# smartwatch_class_2.net
KiCad netlist of a schematic drawn in EAGLE
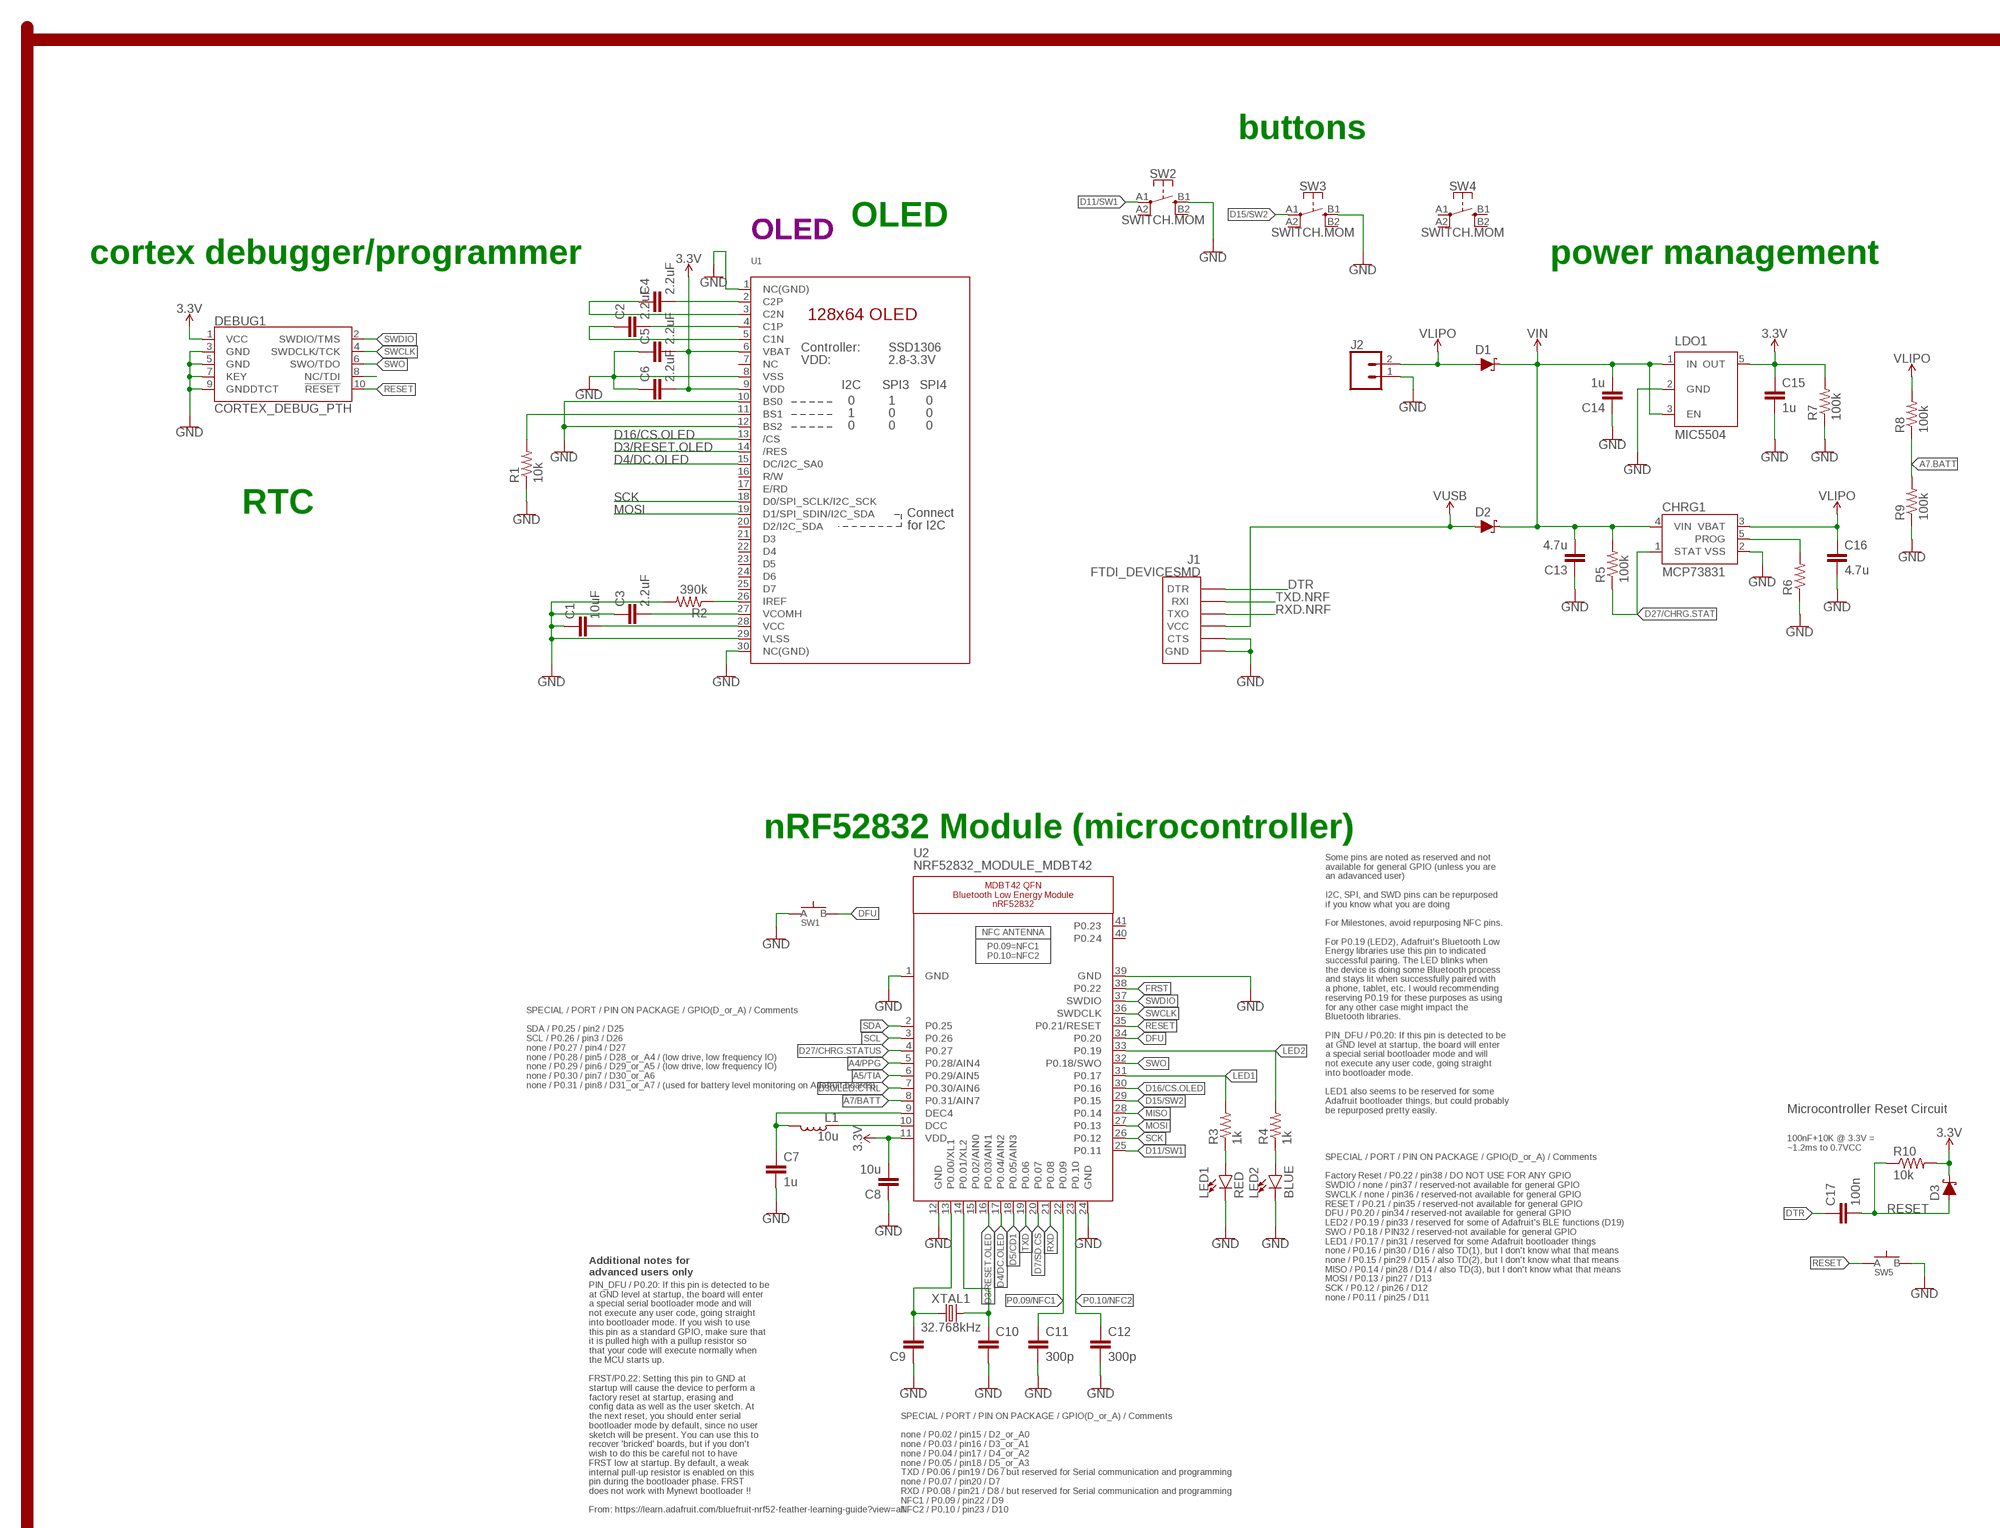
[diagram p0: schematic, sheet 1, part 1 of 2]
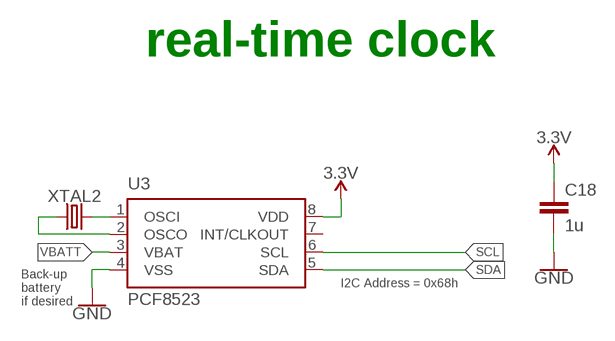
[diagram p1: schematic, sheet 1, part 2 of 2]

(export (version "E")
  (design (tool "Eeschema 10.0.6"))
  (components
    (comp (ref "C1")
      (value "10uF")
      (footprint "eagle-import:C0603")
      (libsource (lib "eagle-import") (part "CAPACITOR0603"))
    )
    (comp (ref "C2")
      (value "2.2uF")
      (footprint "eagle-import:C0402")
      (libsource (lib "eagle-import") (part "CAPACITOR0402"))
    )
    (comp (ref "C3")
      (value "2.2uF")
      (footprint "eagle-import:C0402")
      (libsource (lib "eagle-import") (part "CAPACITOR0402"))
    )
    (comp (ref "C4")
      (value "2.2uF")
      (footprint "eagle-import:C0402")
      (libsource (lib "eagle-import") (part "CAPACITOR0402"))
    )
    (comp (ref "C5")
      (value "2.2uF")
      (footprint "eagle-import:C0402")
      (libsource (lib "eagle-import") (part "CAPACITOR0402"))
    )
    (comp (ref "C6")
      (value "2.2uF")
      (footprint "eagle-import:C0402")
      (libsource (lib "eagle-import") (part "CAPACITOR0402"))
    )
    (comp (ref "C7")
      (value "1u")
      (footprint "eagle-import:C0603")
      (libsource (lib "eagle-import") (part "CAPACITOR0603"))
    )
    (comp (ref "C8")
      (value "10u")
      (footprint "eagle-import:C0805")
      (libsource (lib "eagle-import") (part "CAPACITOR0805"))
    )
    (comp (ref "C9")
      (value "CAPACITOR0603")
      (footprint "eagle-import:C0603")
      (libsource (lib "eagle-import") (part "CAPACITOR0603"))
    )
    (comp (ref "C10")
      (value "CAPACITOR0603")
      (footprint "eagle-import:C0603")
      (libsource (lib "eagle-import") (part "CAPACITOR0603"))
    )
    (comp (ref "C11")
      (value "300p")
      (footprint "eagle-import:C0603")
      (libsource (lib "eagle-import") (part "CAPACITOR0603"))
    )
    (comp (ref "C12")
      (value "300p")
      (footprint "eagle-import:C0603")
      (libsource (lib "eagle-import") (part "CAPACITOR0603"))
    )
    (comp (ref "C13")
      (value "4.7u")
      (footprint "eagle-import:C0603")
      (libsource (lib "eagle-import") (part "CAPACITOR0603"))
    )
    (comp (ref "C14")
      (value "1u")
      (footprint "eagle-import:C0603")
      (libsource (lib "eagle-import") (part "CAPACITOR0603"))
    )
    (comp (ref "C15")
      (value "1u")
      (footprint "eagle-import:C0603")
      (libsource (lib "eagle-import") (part "CAPACITOR0603"))
    )
    (comp (ref "C16")
      (value "4.7u")
      (footprint "eagle-import:C0603")
      (libsource (lib "eagle-import") (part "CAPACITOR0603"))
    )
    (comp (ref "C17")
      (value "100n")
      (footprint "eagle-import:C0603")
      (libsource (lib "eagle-import") (part "CAPACITOR0603"))
    )
    (comp (ref "C18")
      (value "1u")
      (footprint "eagle-import:C0603")
      (libsource (lib "eagle-import") (part "CAPACITOR0603"))
    )
    (comp (ref "CHRG1")
      (value "MCP73831")
      (footprint "eagle-import:SOT23-5")
      (libsource (lib "eagle-import") (part "MCP73831"))
    )
    (comp (ref "D1")
      (value "SCHOTTKY-USC")
      (footprint "eagle-import:USC")
      (libsource (lib "eagle-import") (part "SCHOTTKY-USC"))
    )
    (comp (ref "D2")
      (value "SCHOTTKY-USC")
      (footprint "eagle-import:USC")
      (libsource (lib "eagle-import") (part "SCHOTTKY-USC"))
    )
    (comp (ref "D3")
      (value "SCHOTTKY-USC")
      (footprint "eagle-import:USC")
      (libsource (lib "eagle-import") (part "SCHOTTKY-USC"))
    )
    (comp (ref "DEBUG1")
      (value "CORTEX_DEBUG_PTH")
      (footprint "eagle-import:2X5-PTH-1.27MM")
      (libsource (lib "eagle-import") (part "CORTEX_DEBUG_PTH"))
    )
    (comp (ref "J1")
      (value "FTDI_DEVICESMD")
      (footprint "eagle-import:FTDI-SMD")
      (libsource (lib "eagle-import") (part "FTDI_DEVICESMD"))
    )
    (comp (ref "J2")
      (value "CONN_02")
      (footprint "eagle-import:1X02")
      (libsource (lib "eagle-import") (part "CONN_02"))
    )
    (comp (ref "L1")
      (value "10u")
      (footprint "eagle-import:L0603")
      (libsource (lib "eagle-import") (part "INDUCTOR0603"))
    )
    (comp (ref "LDO1")
      (value "MIC5504")
      (footprint "eagle-import:SOT23-5")
      (libsource (lib "eagle-import") (part "MIC5504"))
    )
    (comp (ref "LED1")
      (value "RED")
      (footprint "eagle-import:LED-0603")
      (libsource (lib "eagle-import") (part "LED0603"))
    )
    (comp (ref "LED2")
      (value "BLUE")
      (footprint "eagle-import:LED-0603")
      (libsource (lib "eagle-import") (part "LED0603"))
    )
    (comp (ref "R1")
      (value "10k")
      (footprint "eagle-import:R0603")
      (libsource (lib "eagle-import") (part "RESISTOR0603"))
    )
    (comp (ref "R2")
      (value "390k")
      (footprint "eagle-import:R0603")
      (libsource (lib "eagle-import") (part "RESISTOR0603"))
    )
    (comp (ref "R3")
      (value "1k")
      (footprint "eagle-import:R0603")
      (libsource (lib "eagle-import") (part "RESISTOR0603"))
    )
    (comp (ref "R4")
      (value "1k")
      (footprint "eagle-import:R0603")
      (libsource (lib "eagle-import") (part "RESISTOR0603"))
    )
    (comp (ref "R5")
      (value "100k")
      (footprint "eagle-import:R0603")
      (libsource (lib "eagle-import") (part "RESISTOR0603"))
    )
    (comp (ref "R6")
      (value "RESISTOR0603")
      (footprint "eagle-import:R0603")
      (libsource (lib "eagle-import") (part "RESISTOR0603"))
    )
    (comp (ref "R7")
      (value "100k")
      (footprint "eagle-import:R0603")
      (libsource (lib "eagle-import") (part "RESISTOR0603"))
    )
    (comp (ref "R8")
      (value "100k")
      (footprint "eagle-import:R0603")
      (libsource (lib "eagle-import") (part "RESISTOR0603"))
    )
    (comp (ref "R9")
      (value "100k")
      (footprint "eagle-import:R0603")
      (libsource (lib "eagle-import") (part "RESISTOR0603"))
    )
    (comp (ref "R10")
      (value "10k")
      (footprint "eagle-import:R0603")
      (libsource (lib "eagle-import") (part "RESISTOR0603"))
    )
    (comp (ref "SW1")
      (value "SPST-PTS830GG140-COPY.1-3")
      (footprint "eagle-import:BUTTON-GULLWING")
      (libsource (lib "eagle-import") (part "SPST-PTS830GG140-COPY.1-3"))
    )
    (comp (ref "SW2")
      (value "SWITCH.MOM")
      (footprint "eagle-import:TACTILE_SWITCH_SMD_6.2MM_TALL")
      (libsource (lib "eagle-import") (part "SWITCH.MOM"))
    )
    (comp (ref "SW3")
      (value "SWITCH.MOM")
      (footprint "eagle-import:TACTILE_SWITCH_SMD_6.2MM_TALL")
      (libsource (lib "eagle-import") (part "SWITCH.MOM"))
    )
    (comp (ref "SW4")
      (value "SWITCH.MOM")
      (footprint "eagle-import:TACTILE_SWITCH_SMD_6.2MM_TALL")
      (libsource (lib "eagle-import") (part "SWITCH.MOM"))
    )
    (comp (ref "SW5")
      (value "SPST-PTS830GG140-COPY.1-3")
      (footprint "eagle-import:BUTTON-GULLWING")
      (libsource (lib "eagle-import") (part "SPST-PTS830GG140-COPY.1-3"))
    )
    (comp (ref "U1")
      (value "DISP_OLED_UG-2864HSWEG01-NO-WRAPAROUND")
      (footprint "eagle-import:UG-2864HSWEG01_0.96IN_NO-WRAPAROUND")
      (libsource (lib "eagle-import") (part "DISP_OLED_UG-2864HSWEG01-NO-WRAPAROUND"))
    )
    (comp (ref "U2")
      (value "NRF52832_MODULE_MDBT42")
      (footprint "eagle-import:BLE_MODULE_RAYTAC_MDBT42")
      (libsource (lib "eagle-import") (part "NRF52832_MODULE_MDBT42"))
    )
    (comp (ref "U3")
      (value "PCF8523")
      (footprint "eagle-import:SO8")
      (libsource (lib "eagle-import") (part "PCF8523"))
    )
    (comp (ref "XTAL1")
      (value "32.768kHz")
      (footprint "eagle-import:2-SMD.NOLEAD.2.0MMTO1.2MM")
      (libsource (lib "eagle-import") (part "CRYSTALECS-.327-12.5-12-C-TR"))
    )
    (comp (ref "XTAL2")
      (value "32.7680kHz")
      (footprint "eagle-import:2-SMD.NOLEAD.2.0MMTO1.2MM")
      (fields (field (name "FREQ") "32.7680KHZ"))
      (libsource (lib "eagle-import") (part "CRYSTALECS-.327-12.5-12-C-TR"))
    )
  )
  (nets
    (net (code "1") (name "/RXD.NRF") (class "Default")
      (node (ref "J1") (pin "TXO") (pinfunction "TXO_TXO") (pintype "bidirectional"))
    )
    (net (code "2") (name "/TXD.NRF") (class "Default")
      (node (ref "J1") (pin "RXI") (pinfunction "RXI_RXI") (pintype "bidirectional"))
    )
    (net (code "3") (name "3.3V") (class "Default")
      (node (ref "C15") (pin "1") (pinfunction "1_1") (pintype "passive"))
      (node (ref "C18") (pin "1") (pinfunction "1_1") (pintype "passive"))
      (node (ref "C5") (pin "2") (pinfunction "2_2") (pintype "passive"))
      (node (ref "C6") (pin "2") (pinfunction "2_2") (pintype "passive"))
      (node (ref "C8") (pin "2") (pinfunction "2_2") (pintype "passive"))
      (node (ref "D3") (pin "-") (pinfunction "C_-") (pintype "passive"))
      (node (ref "DEBUG1") (pin "1") (pinfunction "VCC_1") (pintype "bidirectional"))
      (node (ref "LDO1") (pin "5") (pinfunction "OUT_5") (pintype "bidirectional"))
      (node (ref "R10") (pin "2") (pinfunction "2_2") (pintype "passive"))
      (node (ref "R7") (pin "2") (pinfunction "2_2") (pintype "passive"))
      (node (ref "U1") (pin "6") (pinfunction "VBAT_6") (pintype "input"))
      (node (ref "U1") (pin "9") (pinfunction "VDD_9") (pintype "power_in"))
      (node (ref "U2") (pin "11") (pinfunction "VDD_11") (pintype "bidirectional"))
      (node (ref "U3") (pin "8") (pinfunction "VDD_8") (pintype "power_in"))
    )
    (net (code "4") (name "A4{slash}PPG") (class "Default")
      (node (ref "U2") (pin "5") (pinfunction "P0.28/AIN4_5") (pintype "bidirectional"))
    )
    (net (code "5") (name "A5{slash}TIA") (class "Default")
      (node (ref "U2") (pin "6") (pinfunction "P0.29/AIN5_6") (pintype "bidirectional"))
    )
    (net (code "6") (name "A7.BATT") (class "Default")
      (node (ref "R8") (pin "1") (pinfunction "1_1") (pintype "passive"))
      (node (ref "R9") (pin "2") (pinfunction "2_2") (pintype "passive"))
    )
    (net (code "7") (name "A7{slash}BATT") (class "Default")
      (node (ref "U2") (pin "8") (pinfunction "P0.31/AIN7_8") (pintype "bidirectional"))
    )
    (net (code "8") (name "D3{slash}RESET.OLED") (class "Default")
      (node (ref "U1") (pin "14") (pinfunction "/RES_14") (pintype "input"))
      (node (ref "U2") (pin "16") (pinfunction "P0.03/AIN1_16") (pintype "bidirectional"))
    )
    (net (code "9") (name "D4{slash}DC.OLED") (class "Default")
      (node (ref "U1") (pin "15") (pinfunction "DC/I2C_SA0_15") (pintype "input"))
      (node (ref "U2") (pin "17") (pinfunction "P0.04/AIN2_17") (pintype "bidirectional"))
    )
    (net (code "10") (name "D5{slash}CD1") (class "Default")
      (node (ref "U2") (pin "18") (pinfunction "P0.05/AIN3_18") (pintype "bidirectional"))
    )
    (net (code "11") (name "D7{slash}SD.CS") (class "Default")
      (node (ref "U2") (pin "20") (pinfunction "P0.07_20") (pintype "bidirectional"))
    )
    (net (code "12") (name "D11{slash}SW1") (class "Default")
      (node (ref "SW2") (pin "A1") (pinfunction "1_A1") (pintype "passive"))
      (node (ref "U2") (pin "25") (pinfunction "P0.11_25") (pintype "bidirectional"))
    )
    (net (code "13") (name "D15{slash}SW2") (class "Default")
      (node (ref "SW3") (pin "A1") (pinfunction "1_A1") (pintype "passive"))
      (node (ref "U2") (pin "29") (pinfunction "P0.15_29") (pintype "bidirectional"))
    )
    (net (code "14") (name "D16{slash}CS.OLED") (class "Default")
      (node (ref "U1") (pin "13") (pinfunction "/CS_13") (pintype "input"))
      (node (ref "U2") (pin "30") (pinfunction "P0.16_30") (pintype "bidirectional"))
    )
    (net (code "15") (name "D27{slash}CHRG.STAT") (class "Default")
      (node (ref "CHRG1") (pin "1") (pinfunction "STAT_1") (pintype "output"))
      (node (ref "R5") (pin "1") (pinfunction "1_1") (pintype "passive"))
    )
    (net (code "16") (name "D27{slash}CHRG.STATUS") (class "Default")
      (node (ref "U2") (pin "4") (pinfunction "P0.27_4") (pintype "bidirectional"))
    )
    (net (code "17") (name "D30{slash}LED.CTRL") (class "Default")
      (node (ref "U2") (pin "7") (pinfunction "P0.30/AIN6_7") (pintype "bidirectional"))
    )
    (net (code "18") (name "DFU") (class "Default")
      (node (ref "SW1") (pin "3") (pinfunction "B_3") (pintype "bidirectional"))
      (node (ref "U2") (pin "34") (pinfunction "P0.20_34") (pintype "bidirectional"))
    )
    (net (code "19") (name "DTR") (class "Default")
      (node (ref "C17") (pin "1") (pinfunction "1_1") (pintype "passive"))
      (node (ref "J1") (pin "DTR") (pinfunction "DTR_DTR") (pintype "bidirectional"))
    )
    (net (code "20") (name "FRST") (class "Default")
      (node (ref "U2") (pin "38") (pinfunction "P0.22_38") (pintype "bidirectional"))
    )
    (net (code "21") (name "GND") (class "Default")
      (node (ref "C1") (pin "1") (pinfunction "1_1") (pintype "passive"))
      (node (ref "C10") (pin "2") (pinfunction "2_2") (pintype "passive"))
      (node (ref "C11") (pin "2") (pinfunction "2_2") (pintype "passive"))
      (node (ref "C12") (pin "2") (pinfunction "2_2") (pintype "passive"))
      (node (ref "C13") (pin "1") (pinfunction "1_1") (pintype "passive"))
      (node (ref "C14") (pin "1") (pinfunction "1_1") (pintype "passive"))
      (node (ref "C15") (pin "2") (pinfunction "2_2") (pintype "passive"))
      (node (ref "C16") (pin "2") (pinfunction "2_2") (pintype "passive"))
      (node (ref "C18") (pin "2") (pinfunction "2_2") (pintype "passive"))
      (node (ref "C3") (pin "1") (pinfunction "1_1") (pintype "passive"))
      (node (ref "C5") (pin "1") (pinfunction "1_1") (pintype "passive"))
      (node (ref "C6") (pin "1") (pinfunction "1_1") (pintype "passive"))
      (node (ref "C7") (pin "2") (pinfunction "2_2") (pintype "passive"))
      (node (ref "C8") (pin "1") (pinfunction "1_1") (pintype "passive"))
      (node (ref "C9") (pin "1") (pinfunction "1_1") (pintype "passive"))
      (node (ref "CHRG1") (pin "2") (pinfunction "VSS_2") (pintype "power_in"))
      (node (ref "DEBUG1") (pin "3") (pinfunction "GND_3") (pintype "bidirectional"))
      (node (ref "DEBUG1") (pin "5") (pinfunction "GND_5") (pintype "bidirectional"))
      (node (ref "DEBUG1") (pin "7") (pinfunction "KEY_7") (pintype "bidirectional"))
      (node (ref "DEBUG1") (pin "9") (pinfunction "GNDDTCT_9") (pintype "bidirectional"))
      (node (ref "J1") (pin "CTS") (pinfunction "CTS_CTS") (pintype "bidirectional"))
      (node (ref "J1") (pin "GND") (pinfunction "GND_GND") (pintype "bidirectional"))
      (node (ref "J2") (pin "1") (pinfunction "1_1") (pintype "passive"))
      (node (ref "LDO1") (pin "2") (pinfunction "GND_2") (pintype "bidirectional"))
      (node (ref "LED1") (pin "C") (pinfunction "C_C") (pintype "passive"))
      (node (ref "LED2") (pin "C") (pinfunction "C_C") (pintype "passive"))
      (node (ref "R1") (pin "1") (pinfunction "1_1") (pintype "passive"))
      (node (ref "R2") (pin "2") (pinfunction "2_2") (pintype "passive"))
      (node (ref "R6") (pin "1") (pinfunction "1_1") (pintype "passive"))
      (node (ref "R7") (pin "1") (pinfunction "1_1") (pintype "passive"))
      (node (ref "R9") (pin "1") (pinfunction "1_1") (pintype "passive"))
      (node (ref "SW1") (pin "1") (pinfunction "A_1") (pintype "bidirectional"))
      (node (ref "SW2") (pin "B1") (pinfunction "3_B1") (pintype "passive"))
      (node (ref "SW3") (pin "B1") (pinfunction "3_B1") (pintype "passive"))
      (node (ref "SW5") (pin "3") (pinfunction "B_3") (pintype "bidirectional"))
      (node (ref "U1") (pin "1") (pinfunction "NC(GND)_1") (pintype "input"))
      (node (ref "U1") (pin "10") (pinfunction "BS0_10") (pintype "input"))
      (node (ref "U1") (pin "12") (pinfunction "BS2_12") (pintype "input"))
      (node (ref "U1") (pin "29") (pinfunction "VLSS_29") (pintype "power_in"))
      (node (ref "U1") (pin "30") (pinfunction "NC(GND)_30") (pintype "input"))
      (node (ref "U1") (pin "8") (pinfunction "VSS_8") (pintype "power_in"))
      (node (ref "U2") (pin "1") (pinfunction "GND_1") (pintype "bidirectional"))
      (node (ref "U2") (pin "12") (pinfunction "GND_12") (pintype "bidirectional"))
      (node (ref "U2") (pin "24") (pinfunction "GND_24") (pintype "bidirectional"))
      (node (ref "U2") (pin "39") (pinfunction "GND_39") (pintype "bidirectional"))
      (node (ref "U3") (pin "4") (pinfunction "VSS_4") (pintype "power_in"))
    )
    (net (code "22") (name "LED1") (class "Default")
      (node (ref "R3") (pin "2") (pinfunction "2_2") (pintype "passive"))
      (node (ref "U2") (pin "31") (pinfunction "P0.17_31") (pintype "bidirectional"))
    )
    (net (code "23") (name "LED2") (class "Default")
      (node (ref "R4") (pin "2") (pinfunction "2_2") (pintype "passive"))
      (node (ref "U2") (pin "33") (pinfunction "P0.19_33") (pintype "bidirectional"))
    )
    (net (code "24") (name "MISO") (class "Default")
      (node (ref "U2") (pin "28") (pinfunction "P0.14_28") (pintype "bidirectional"))
    )
    (net (code "25") (name "MOSI") (class "Default")
      (node (ref "U1") (pin "19") (pinfunction "D1/SPI_SDIN/I2C_SDA_19") (pintype "bidirectional"))
      (node (ref "U2") (pin "27") (pinfunction "P0.13_27") (pintype "bidirectional"))
    )
    (net (code "26") (name "Net-(CHRG1-PROG)") (class "Default")
      (node (ref "CHRG1") (pin "5") (pinfunction "PROG_5") (pintype "input"))
      (node (ref "R6") (pin "2") (pinfunction "2_2") (pintype "passive"))
    )
    (net (code "27") (name "Net-(LED1-PadA)") (class "Default")
      (node (ref "LED1") (pin "A") (pinfunction "A_A") (pintype "passive"))
      (node (ref "R3") (pin "1") (pinfunction "1_1") (pintype "passive"))
    )
    (net (code "28") (name "Net-(LED2-PadA)") (class "Default")
      (node (ref "LED2") (pin "A") (pinfunction "A_A") (pintype "passive"))
      (node (ref "R4") (pin "1") (pinfunction "1_1") (pintype "passive"))
    )
    (net (code "29") (name "Net-(U1-BS1)") (class "Default")
      (node (ref "R1") (pin "2") (pinfunction "2_2") (pintype "passive"))
      (node (ref "U1") (pin "11") (pinfunction "BS1_11") (pintype "input"))
    )
    (net (code "30") (name "Net-(U1-C1N)") (class "Default")
      (node (ref "C2") (pin "1") (pinfunction "1_1") (pintype "passive"))
      (node (ref "U1") (pin "5") (pinfunction "C1N_5") (pintype "input"))
    )
    (net (code "31") (name "Net-(U1-C1P)") (class "Default")
      (node (ref "C2") (pin "2") (pinfunction "2_2") (pintype "passive"))
      (node (ref "U1") (pin "4") (pinfunction "C1P_4") (pintype "input"))
    )
    (net (code "32") (name "Net-(U1-C2N)") (class "Default")
      (node (ref "C4") (pin "1") (pinfunction "1_1") (pintype "passive"))
      (node (ref "U1") (pin "3") (pinfunction "C2N_3") (pintype "input"))
    )
    (net (code "33") (name "Net-(U1-C2P)") (class "Default")
      (node (ref "C4") (pin "2") (pinfunction "2_2") (pintype "passive"))
      (node (ref "U1") (pin "2") (pinfunction "C2P_2") (pintype "input"))
    )
    (net (code "34") (name "Net-(U1-IREF)") (class "Default")
      (node (ref "R2") (pin "1") (pinfunction "1_1") (pintype "passive"))
      (node (ref "U1") (pin "26") (pinfunction "IREF_26") (pintype "input"))
    )
    (net (code "35") (name "Net-(U1-VCC)") (class "Default")
      (node (ref "C1") (pin "2") (pinfunction "2_2") (pintype "passive"))
      (node (ref "U1") (pin "28") (pinfunction "VCC_28") (pintype "power_in"))
    )
    (net (code "36") (name "Net-(U1-VCOMH)") (class "Default")
      (node (ref "C3") (pin "2") (pinfunction "2_2") (pintype "passive"))
      (node (ref "U1") (pin "27") (pinfunction "VCOMH_27") (pintype "output"))
    )
    (net (code "37") (name "Net-(U2-DCC)") (class "Default")
      (node (ref "L1") (pin "1") (pinfunction "1_1") (pintype "passive"))
      (node (ref "U2") (pin "10") (pinfunction "DCC_10") (pintype "bidirectional"))
    )
    (net (code "38") (name "Net-(U2-DEC4)") (class "Default")
      (node (ref "C7") (pin "1") (pinfunction "1_1") (pintype "passive"))
      (node (ref "L1") (pin "2") (pinfunction "2_2") (pintype "passive"))
      (node (ref "U2") (pin "9") (pinfunction "DEC4_9") (pintype "bidirectional"))
    )
    (net (code "39") (name "Net-(U2-P0.00{slash}XL1)") (class "Default")
      (node (ref "C9") (pin "2") (pinfunction "2_2") (pintype "passive"))
      (node (ref "U2") (pin "13") (pinfunction "P0.00/XL1_13") (pintype "bidirectional"))
      (node (ref "XTAL1") (pin "P$1") (pinfunction "1_P$1") (pintype "passive"))
    )
    (net (code "40") (name "Net-(U2-P0.01{slash}XL2)") (class "Default")
      (node (ref "C10") (pin "1") (pinfunction "1_1") (pintype "passive"))
      (node (ref "U2") (pin "14") (pinfunction "P0.01/XL2_14") (pintype "bidirectional"))
      (node (ref "XTAL1") (pin "P$2") (pinfunction "2_P$2") (pintype "passive"))
    )
    (net (code "41") (name "Net-(U3-OSCI)") (class "Default")
      (node (ref "U3") (pin "1") (pinfunction "OSCI_1") (pintype "bidirectional"))
      (node (ref "XTAL2") (pin "P$2") (pinfunction "2_P$2") (pintype "passive"))
    )
    (net (code "42") (name "Net-(U3-OSCO)") (class "Default")
      (node (ref "U3") (pin "2") (pinfunction "OSCO_2") (pintype "bidirectional"))
      (node (ref "XTAL2") (pin "P$1") (pinfunction "1_P$1") (pintype "passive"))
    )
    (net (code "43") (name "P0.09{slash}NFC1") (class "Default")
      (node (ref "C11") (pin "1") (pinfunction "1_1") (pintype "passive"))
      (node (ref "U2") (pin "22") (pinfunction "P0.09_22") (pintype "bidirectional"))
    )
    (net (code "44") (name "P0.10{slash}NFC2") (class "Default")
      (node (ref "C12") (pin "1") (pinfunction "1_1") (pintype "passive"))
      (node (ref "U2") (pin "23") (pinfunction "P0.10_23") (pintype "bidirectional"))
    )
    (net (code "45") (name "RESET") (class "Default")
      (node (ref "C17") (pin "2") (pinfunction "2_2") (pintype "passive"))
      (node (ref "D3") (pin "+") (pinfunction "A_+") (pintype "passive"))
      (node (ref "DEBUG1") (pin "10") (pinfunction "~{RESET}_10") (pintype "bidirectional"))
      (node (ref "R10") (pin "1") (pinfunction "1_1") (pintype "passive"))
      (node (ref "SW5") (pin "1") (pinfunction "A_1") (pintype "bidirectional"))
      (node (ref "U2") (pin "35") (pinfunction "P0.21/RESET_35") (pintype "bidirectional"))
    )
    (net (code "46") (name "RXD") (class "Default")
      (node (ref "U2") (pin "21") (pinfunction "P0.08_21") (pintype "bidirectional"))
    )
    (net (code "47") (name "SCK") (class "Default")
      (node (ref "U1") (pin "18") (pinfunction "D0/SPI_SCLK/I2C_SCK_18") (pintype "bidirectional"))
      (node (ref "U2") (pin "26") (pinfunction "P0.12_26") (pintype "bidirectional"))
    )
    (net (code "48") (name "SCL") (class "Default")
      (node (ref "U2") (pin "3") (pinfunction "P0.26_3") (pintype "bidirectional"))
      (node (ref "U3") (pin "6") (pinfunction "SCL_6") (pintype "bidirectional"))
    )
    (net (code "49") (name "SDA") (class "Default")
      (node (ref "U2") (pin "2") (pinfunction "P0.25_2") (pintype "bidirectional"))
      (node (ref "U3") (pin "5") (pinfunction "SDA_5") (pintype "bidirectional"))
    )
    (net (code "50") (name "SWCLK") (class "Default")
      (node (ref "DEBUG1") (pin "4") (pinfunction "SWDCLK/TCK_4") (pintype "bidirectional"))
      (node (ref "U2") (pin "36") (pinfunction "SWDCLK_36") (pintype "bidirectional"))
    )
    (net (code "51") (name "SWDIO") (class "Default")
      (node (ref "DEBUG1") (pin "2") (pinfunction "SWDIO/TMS_2") (pintype "bidirectional"))
      (node (ref "U2") (pin "37") (pinfunction "SWDIO_37") (pintype "bidirectional"))
    )
    (net (code "52") (name "SWO") (class "Default")
      (node (ref "DEBUG1") (pin "6") (pinfunction "SWO/TDO_6") (pintype "bidirectional"))
      (node (ref "U2") (pin "32") (pinfunction "P0.18/SWO_32") (pintype "bidirectional"))
    )
    (net (code "53") (name "TXD") (class "Default")
      (node (ref "U2") (pin "19") (pinfunction "P0.06_19") (pintype "bidirectional"))
    )
    (net (code "54") (name "VBATT") (class "Default")
      (node (ref "U3") (pin "3") (pinfunction "VBAT_3") (pintype "power_in"))
    )
    (net (code "55") (name "VIN") (class "Default")
      (node (ref "C13") (pin "2") (pinfunction "2_2") (pintype "passive"))
      (node (ref "C14") (pin "2") (pinfunction "2_2") (pintype "passive"))
      (node (ref "CHRG1") (pin "4") (pinfunction "VIN_4") (pintype "power_in"))
      (node (ref "D1") (pin "-") (pinfunction "C_-") (pintype "passive"))
      (node (ref "D2") (pin "-") (pinfunction "C_-") (pintype "passive"))
      (node (ref "LDO1") (pin "1") (pinfunction "IN_1") (pintype "bidirectional"))
      (node (ref "LDO1") (pin "3") (pinfunction "EN_3") (pintype "bidirectional"))
      (node (ref "R5") (pin "2") (pinfunction "2_2") (pintype "passive"))
    )
    (net (code "56") (name "VLIPO") (class "Default")
      (node (ref "C16") (pin "1") (pinfunction "1_1") (pintype "passive"))
      (node (ref "CHRG1") (pin "3") (pinfunction "VBAT_3") (pintype "power_in"))
      (node (ref "D1") (pin "+") (pinfunction "A_+") (pintype "passive"))
      (node (ref "J2") (pin "2") (pinfunction "2_2") (pintype "passive"))
      (node (ref "R8") (pin "2") (pinfunction "2_2") (pintype "passive"))
    )
    (net (code "57") (name "VUSB") (class "Default")
      (node (ref "D2") (pin "+") (pinfunction "A_+") (pintype "passive"))
      (node (ref "J1") (pin "VCC") (pinfunction "VCC_VCC") (pintype "bidirectional"))
    )
    (net (code "58") (name "unconnected-(DEBUG1-NC{slash}TDI-Pad8)") (class "Default")
      (node (ref "DEBUG1") (pin "8") (pinfunction "NC/TDI_8") (pintype "bidirectional"))
    )
    (net (code "59") (name "unconnected-(SW2-2-PadA2)") (class "Default")
      (node (ref "SW2") (pin "A2") (pinfunction "2_A2") (pintype "passive"))
    )
    (net (code "60") (name "unconnected-(SW2-4-PadB2)") (class "Default")
      (node (ref "SW2") (pin "B2") (pinfunction "4_B2") (pintype "passive"))
    )
    (net (code "61") (name "unconnected-(SW3-2-PadA2)") (class "Default")
      (node (ref "SW3") (pin "A2") (pinfunction "2_A2") (pintype "passive"))
    )
    (net (code "62") (name "unconnected-(SW3-4-PadB2)") (class "Default")
      (node (ref "SW3") (pin "B2") (pinfunction "4_B2") (pintype "passive"))
    )
    (net (code "63") (name "unconnected-(SW4-1-PadA1)") (class "Default")
      (node (ref "SW4") (pin "A1") (pinfunction "1_A1") (pintype "passive"))
    )
    (net (code "64") (name "unconnected-(SW4-2-PadA2)") (class "Default")
      (node (ref "SW4") (pin "A2") (pinfunction "2_A2") (pintype "passive"))
    )
    (net (code "65") (name "unconnected-(SW4-3-PadB1)") (class "Default")
      (node (ref "SW4") (pin "B1") (pinfunction "3_B1") (pintype "passive"))
    )
    (net (code "66") (name "unconnected-(SW4-4-PadB2)") (class "Default")
      (node (ref "SW4") (pin "B2") (pinfunction "4_B2") (pintype "passive"))
    )
    (net (code "67") (name "unconnected-(U1-D2{slash}I2C_SDA-Pad20)") (class "Default")
      (node (ref "U1") (pin "20") (pinfunction "D2/I2C_SDA_20") (pintype "bidirectional"))
    )
    (net (code "68") (name "unconnected-(U1-D3-Pad21)") (class "Default")
      (node (ref "U1") (pin "21") (pinfunction "D3_21") (pintype "bidirectional"))
    )
    (net (code "69") (name "unconnected-(U1-D4-Pad22)") (class "Default")
      (node (ref "U1") (pin "22") (pinfunction "D4_22") (pintype "bidirectional"))
    )
    (net (code "70") (name "unconnected-(U1-D5-Pad23)") (class "Default")
      (node (ref "U1") (pin "23") (pinfunction "D5_23") (pintype "bidirectional"))
    )
    (net (code "71") (name "unconnected-(U1-D6-Pad24)") (class "Default")
      (node (ref "U1") (pin "24") (pinfunction "D6_24") (pintype "bidirectional"))
    )
    (net (code "72") (name "unconnected-(U1-D7-Pad25)") (class "Default")
      (node (ref "U1") (pin "25") (pinfunction "D7_25") (pintype "bidirectional"))
    )
    (net (code "73") (name "unconnected-(U1-E{slash}RD-Pad17)") (class "Default")
      (node (ref "U1") (pin "17") (pinfunction "E/RD_17") (pintype "input"))
    )
    (net (code "74") (name "unconnected-(U1-NC-Pad7)") (class "Default")
      (node (ref "U1") (pin "7") (pinfunction "NC_7") (pintype "no_connect"))
    )
    (net (code "75") (name "unconnected-(U1-R{slash}W-Pad16)") (class "Default")
      (node (ref "U1") (pin "16") (pinfunction "R/W_16") (pintype "input"))
    )
    (net (code "76") (name "unconnected-(U2-P0.02{slash}AIN0-Pad15)") (class "Default")
      (node (ref "U2") (pin "15") (pinfunction "P0.02/AIN0_15") (pintype "bidirectional"))
    )
    (net (code "77") (name "unconnected-(U2-P0.23-Pad41)") (class "Default")
      (node (ref "U2") (pin "41") (pinfunction "P0.23_41") (pintype "bidirectional"))
    )
    (net (code "78") (name "unconnected-(U2-P0.24-Pad40)") (class "Default")
      (node (ref "U2") (pin "40") (pinfunction "P0.24_40") (pintype "bidirectional"))
    )
    (net (code "79") (name "unconnected-(U3-INT{slash}CLKOUT-Pad7)") (class "Default")
      (node (ref "U3") (pin "7") (pinfunction "INT/CLKOUT_7") (pintype "bidirectional"))
    )
  )
)
